# board.net
KiCad netlist of a schematic drawn in EAGLE
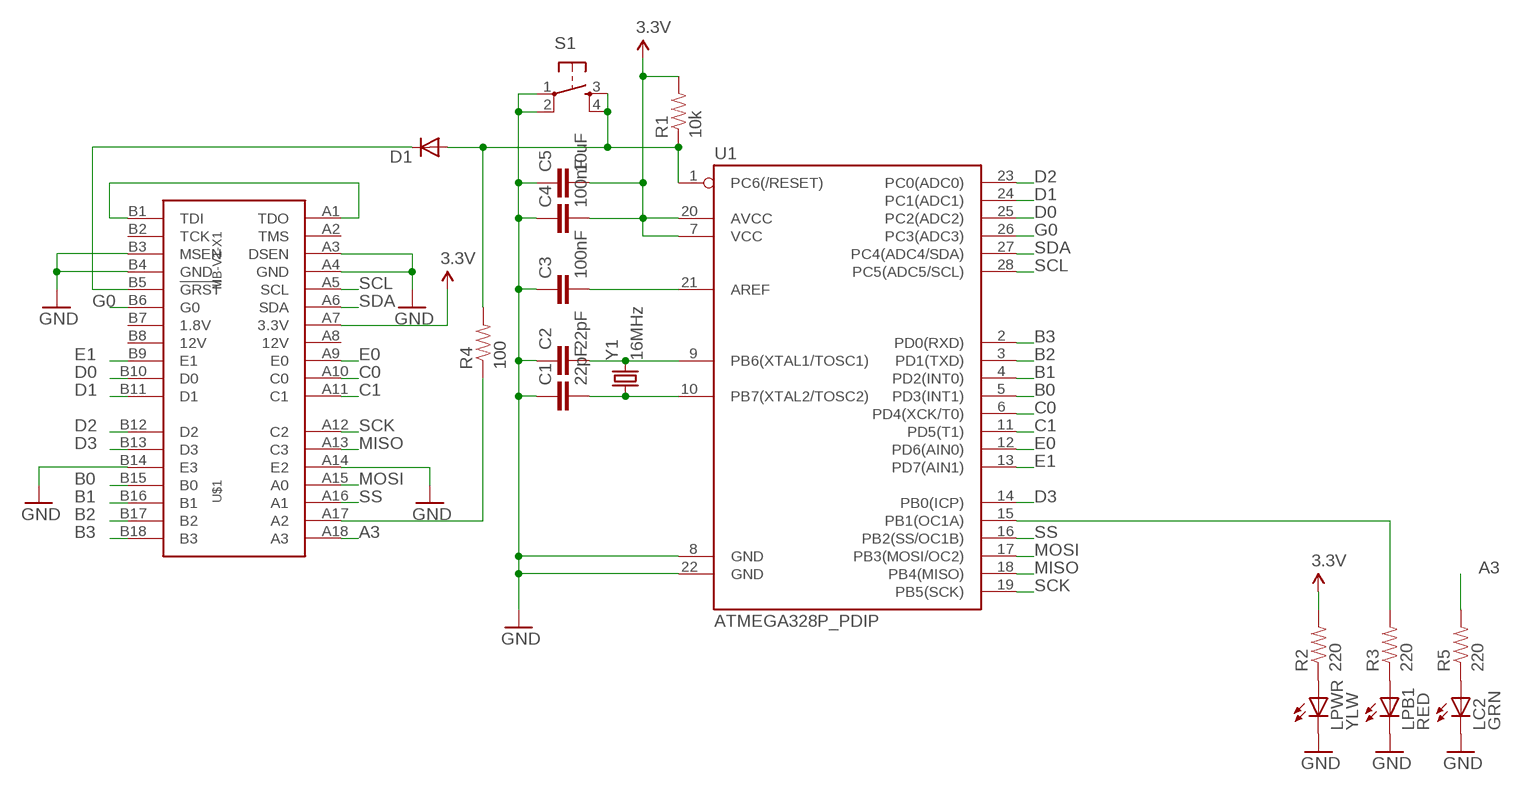
[diagram p0: schematic, sheet 1]

(export (version "E")
  (design (tool "Eeschema 10.0.6"))
  (components
    (comp (ref "C1")
      (value "22pF")
      (footprint "eagle-import:0402-CAP")
      (libsource (lib "eagle-import") (part "CAP0402-CAP"))
    )
    (comp (ref "C2")
      (value "22pF")
      (footprint "eagle-import:0402-CAP")
      (libsource (lib "eagle-import") (part "CAP0402-CAP"))
    )
    (comp (ref "C3")
      (value "100nF")
      (footprint "eagle-import:0402-CAP")
      (libsource (lib "eagle-import") (part "CAP0402-CAP"))
    )
    (comp (ref "C4")
      (value "100nF")
      (footprint "eagle-import:0402-CAP")
      (libsource (lib "eagle-import") (part "CAP0402-CAP"))
    )
    (comp (ref "C5")
      (value "10uF")
      (footprint "eagle-import:0805")
      (libsource (lib "eagle-import") (part "CAP0805"))
    )
    (comp (ref "D1")
      (value "DIODE1N4148")
      (footprint "eagle-import:DIODE-1N4148")
      (libsource (lib "eagle-import") (part "DIODE1N4148"))
    )
    (comp (ref "LC2")
      (value "GRN")
      (footprint "eagle-import:LED-0603")
      (libsource (lib "eagle-import") (part "LED-RED0603"))
    )
    (comp (ref "LPB1")
      (value "RED")
      (footprint "eagle-import:LED-0603")
      (libsource (lib "eagle-import") (part "LED-RED0603"))
    )
    (comp (ref "LPWR")
      (value "YLW")
      (footprint "eagle-import:LED-0603")
      (libsource (lib "eagle-import") (part "LED-RED0603"))
    )
    (comp (ref "R1")
      (value "10k")
      (footprint "eagle-import:0603-RES")
      (libsource (lib "eagle-import") (part "kmod-passives_RESISTOR0603"))
    )
    (comp (ref "R2")
      (value "220")
      (footprint "eagle-import:0603-RES")
      (libsource (lib "eagle-import") (part "RESISTOR0603"))
    )
    (comp (ref "R3")
      (value "220")
      (footprint "eagle-import:0603-RES")
      (libsource (lib "eagle-import") (part "RESISTOR0603"))
    )
    (comp (ref "R4")
      (value "100")
      (footprint "eagle-import:0603-RES")
      (libsource (lib "eagle-import") (part "kmod-passives_RESISTOR0603"))
    )
    (comp (ref "R5")
      (value "220")
      (footprint "eagle-import:0603-RES")
      (libsource (lib "eagle-import") (part "RESISTOR0603"))
    )
    (comp (ref "S1")
      (value "TAC_SWITCHPTH")
      (footprint "eagle-import:TACTILE-PTH")
      (libsource (lib "eagle-import") (part "TAC_SWITCHPTH"))
    )
    (comp (ref "U$1")
      (value "MB-V1-X1")
      (footprint "eagle-import:PCIE-X1-EDGE")
      (libsource (lib "eagle-import") (part "MB-V1-X1"))
    )
    (comp (ref "U1")
      (value "ATMEGA328P_PDIP")
      (footprint "eagle-import:DIL28-3")
      (libsource (lib "eagle-import") (part "ATMEGA328P_PDIP"))
    )
    (comp (ref "Y1")
      (value "16MHz")
      (footprint "eagle-import:HC49US")
      (libsource (lib "eagle-import") (part "CRYSTALHC49US"))
    )
  )
  (nets
    (net (code "1") (name "/A3") (class "Default")
      (node (ref "R5") (pin "2") (pinfunction "2_2") (pintype "passive"))
      (node (ref "U$1") (pin "A18") (pinfunction "A3_A18") (pintype "bidirectional"))
    )
    (net (code "2") (name "/B0") (class "Default")
      (node (ref "U$1") (pin "B15") (pinfunction "B0_B15") (pintype "bidirectional"))
      (node (ref "U1") (pin "5") (pinfunction "PD3(INT1)_5") (pintype "bidirectional"))
    )
    (net (code "3") (name "/B1") (class "Default")
      (node (ref "U$1") (pin "B16") (pinfunction "B1_B16") (pintype "bidirectional"))
      (node (ref "U1") (pin "4") (pinfunction "PD2(INT0)_4") (pintype "bidirectional"))
    )
    (net (code "4") (name "/B2") (class "Default")
      (node (ref "U$1") (pin "B17") (pinfunction "B2_B17") (pintype "bidirectional"))
      (node (ref "U1") (pin "3") (pinfunction "PD1(TXD)_3") (pintype "bidirectional"))
    )
    (net (code "5") (name "/B3") (class "Default")
      (node (ref "U$1") (pin "B18") (pinfunction "B3_B18") (pintype "bidirectional"))
      (node (ref "U1") (pin "2") (pinfunction "PD0(RXD)_2") (pintype "bidirectional"))
    )
    (net (code "6") (name "/C0") (class "Default")
      (node (ref "U$1") (pin "A10") (pinfunction "C0_A10") (pintype "bidirectional"))
      (node (ref "U1") (pin "6") (pinfunction "PD4(XCK/T0)_6") (pintype "bidirectional"))
    )
    (net (code "7") (name "/C1") (class "Default")
      (node (ref "U$1") (pin "A11") (pinfunction "C1_A11") (pintype "bidirectional"))
      (node (ref "U1") (pin "11") (pinfunction "PD5(T1)_11") (pintype "bidirectional"))
    )
    (net (code "8") (name "/D0") (class "Default")
      (node (ref "U$1") (pin "B10") (pinfunction "D0_B10") (pintype "bidirectional"))
      (node (ref "U1") (pin "25") (pinfunction "PC2(ADC2)_25") (pintype "bidirectional"))
    )
    (net (code "9") (name "/D1") (class "Default")
      (node (ref "U$1") (pin "B11") (pinfunction "D1_B11") (pintype "bidirectional"))
      (node (ref "U1") (pin "24") (pinfunction "PC1(ADC1)_24") (pintype "bidirectional"))
    )
    (net (code "10") (name "/D2") (class "Default")
      (node (ref "U$1") (pin "B12") (pinfunction "D2_B12") (pintype "bidirectional"))
      (node (ref "U1") (pin "23") (pinfunction "PC0(ADC0)_23") (pintype "bidirectional"))
    )
    (net (code "11") (name "/D3") (class "Default")
      (node (ref "U$1") (pin "B13") (pinfunction "D3_B13") (pintype "bidirectional"))
      (node (ref "U1") (pin "14") (pinfunction "PB0(ICP)_14") (pintype "bidirectional"))
    )
    (net (code "12") (name "/E0") (class "Default")
      (node (ref "U$1") (pin "A9") (pinfunction "E0_A9") (pintype "bidirectional"))
      (node (ref "U1") (pin "12") (pinfunction "PD6(AIN0)_12") (pintype "bidirectional"))
    )
    (net (code "13") (name "/E1") (class "Default")
      (node (ref "U$1") (pin "B9") (pinfunction "E1_B9") (pintype "bidirectional"))
      (node (ref "U1") (pin "13") (pinfunction "PD7(AIN1)_13") (pintype "bidirectional"))
    )
    (net (code "14") (name "/G0") (class "Default")
      (node (ref "U$1") (pin "B6") (pinfunction "G0_B6") (pintype "bidirectional"))
      (node (ref "U1") (pin "26") (pinfunction "PC3(ADC3)_26") (pintype "bidirectional"))
    )
    (net (code "15") (name "/MISO") (class "Default")
      (node (ref "U$1") (pin "A13") (pinfunction "C3_A13") (pintype "bidirectional"))
      (node (ref "U1") (pin "18") (pinfunction "PB4(MISO)_18") (pintype "bidirectional"))
    )
    (net (code "16") (name "/MOSI") (class "Default")
      (node (ref "U$1") (pin "A15") (pinfunction "A0_A15") (pintype "bidirectional"))
      (node (ref "U1") (pin "17") (pinfunction "PB3(MOSI/OC2)_17") (pintype "bidirectional"))
    )
    (net (code "17") (name "/SCK") (class "Default")
      (node (ref "U$1") (pin "A12") (pinfunction "C2_A12") (pintype "bidirectional"))
      (node (ref "U1") (pin "19") (pinfunction "PB5(SCK)_19") (pintype "bidirectional"))
    )
    (net (code "18") (name "/SCL") (class "Default")
      (node (ref "U$1") (pin "A5") (pinfunction "SCL_A5") (pintype "bidirectional"))
      (node (ref "U1") (pin "28") (pinfunction "PC5(ADC5/SCL)_28") (pintype "bidirectional"))
    )
    (net (code "19") (name "/SDA") (class "Default")
      (node (ref "U$1") (pin "A6") (pinfunction "SDA_A6") (pintype "bidirectional"))
      (node (ref "U1") (pin "27") (pinfunction "PC4(ADC4/SDA)_27") (pintype "bidirectional"))
    )
    (net (code "20") (name "/SS") (class "Default")
      (node (ref "U$1") (pin "A16") (pinfunction "A1_A16") (pintype "bidirectional"))
      (node (ref "U1") (pin "16") (pinfunction "PB2(SS/OC1B)_16") (pintype "bidirectional"))
    )
    (net (code "21") (name "3.3V") (class "Default")
      (node (ref "C4") (pin "2") (pinfunction "2_2") (pintype "passive"))
      (node (ref "C5") (pin "2") (pinfunction "2_2") (pintype "passive"))
      (node (ref "R1") (pin "2") (pinfunction "2_2") (pintype "passive"))
      (node (ref "R2") (pin "2") (pinfunction "2_2") (pintype "passive"))
      (node (ref "U$1") (pin "A7") (pinfunction "3.3V_A7") (pintype "bidirectional"))
      (node (ref "U1") (pin "20") (pinfunction "AVCC_20") (pintype "bidirectional"))
      (node (ref "U1") (pin "7") (pinfunction "VCC_7") (pintype "bidirectional"))
    )
    (net (code "22") (name "GND") (class "Default")
      (node (ref "C1") (pin "1") (pinfunction "1_1") (pintype "passive"))
      (node (ref "C2") (pin "1") (pinfunction "1_1") (pintype "passive"))
      (node (ref "C3") (pin "1") (pinfunction "1_1") (pintype "passive"))
      (node (ref "C4") (pin "1") (pinfunction "1_1") (pintype "passive"))
      (node (ref "C5") (pin "1") (pinfunction "1_1") (pintype "passive"))
      (node (ref "LC2") (pin "C") (pinfunction "C_C") (pintype "passive"))
      (node (ref "LPB1") (pin "C") (pinfunction "C_C") (pintype "passive"))
      (node (ref "LPWR") (pin "C") (pinfunction "C_C") (pintype "passive"))
      (node (ref "S1") (pin "1") (pinfunction "1_1") (pintype "passive"))
      (node (ref "S1") (pin "2") (pinfunction "2_2") (pintype "passive"))
      (node (ref "U$1") (pin "A14") (pinfunction "E2_A14") (pintype "bidirectional"))
      (node (ref "U$1") (pin "A3") (pinfunction "DSEN_A3") (pintype "bidirectional"))
      (node (ref "U$1") (pin "A4") (pinfunction "GND_A4") (pintype "bidirectional"))
      (node (ref "U$1") (pin "B14") (pinfunction "E3_B14") (pintype "bidirectional"))
      (node (ref "U$1") (pin "B3") (pinfunction "MSEN_B3") (pintype "bidirectional"))
      (node (ref "U$1") (pin "B4") (pinfunction "GND_B4") (pintype "bidirectional"))
      (node (ref "U1") (pin "22") (pinfunction "GND_22") (pintype "bidirectional"))
      (node (ref "U1") (pin "8") (pinfunction "GND_8") (pintype "bidirectional"))
    )
    (net (code "23") (name "Net-(LC2-PadA)") (class "Default")
      (node (ref "LC2") (pin "A") (pinfunction "A_A") (pintype "passive"))
      (node (ref "R5") (pin "1") (pinfunction "1_1") (pintype "passive"))
    )
    (net (code "24") (name "Net-(LPB1-PadA)") (class "Default")
      (node (ref "LPB1") (pin "A") (pinfunction "A_A") (pintype "passive"))
      (node (ref "R3") (pin "1") (pinfunction "1_1") (pintype "passive"))
    )
    (net (code "25") (name "Net-(LPWR-PadA)") (class "Default")
      (node (ref "LPWR") (pin "A") (pinfunction "A_A") (pintype "passive"))
      (node (ref "R2") (pin "1") (pinfunction "1_1") (pintype "passive"))
    )
    (net (code "26") (name "Net-(U$1-A2)") (class "Default")
      (node (ref "R4") (pin "1") (pinfunction "1_1") (pintype "passive"))
      (node (ref "U$1") (pin "A17") (pinfunction "A2_A17") (pintype "bidirectional"))
    )
    (net (code "27") (name "Net-(U$1-TDI)") (class "Default")
      (node (ref "U$1") (pin "A1") (pinfunction "TDO_A1") (pintype "bidirectional"))
      (node (ref "U$1") (pin "B1") (pinfunction "TDI_B1") (pintype "bidirectional"))
    )
    (net (code "28") (name "Net-(U$1-~{GRST})") (class "Default")
      (node (ref "D1") (pin "C") (pinfunction "C_C") (pintype "passive"))
      (node (ref "U$1") (pin "B5") (pinfunction "~{GRST}_B5") (pintype "bidirectional"))
    )
    (net (code "29") (name "Net-(U1-AREF)") (class "Default")
      (node (ref "C3") (pin "2") (pinfunction "2_2") (pintype "passive"))
      (node (ref "U1") (pin "21") (pinfunction "AREF_21") (pintype "bidirectional"))
    )
    (net (code "30") (name "Net-(U1-PB1(OC1A))") (class "Default")
      (node (ref "R3") (pin "2") (pinfunction "2_2") (pintype "passive"))
      (node (ref "U1") (pin "15") (pinfunction "PB1(OC1A)_15") (pintype "bidirectional"))
    )
    (net (code "31") (name "Net-(U1-PB6(XTAL1{slash}TOSC1))") (class "Default")
      (node (ref "C2") (pin "2") (pinfunction "2_2") (pintype "passive"))
      (node (ref "U1") (pin "9") (pinfunction "PB6(XTAL1/TOSC1)_9") (pintype "bidirectional"))
      (node (ref "Y1") (pin "2") (pinfunction "2_2") (pintype "passive"))
    )
    (net (code "32") (name "Net-(U1-PB7(XTAL2{slash}TOSC2))") (class "Default")
      (node (ref "C1") (pin "2") (pinfunction "2_2") (pintype "passive"))
      (node (ref "U1") (pin "10") (pinfunction "PB7(XTAL2/TOSC2)_10") (pintype "bidirectional"))
      (node (ref "Y1") (pin "1") (pinfunction "1_1") (pintype "passive"))
    )
    (net (code "33") (name "Net-(U1-PC6({slash}RESET))") (class "Default")
      (node (ref "D1") (pin "A") (pinfunction "A_A") (pintype "passive"))
      (node (ref "R1") (pin "1") (pinfunction "1_1") (pintype "passive"))
      (node (ref "R4") (pin "2") (pinfunction "2_2") (pintype "passive"))
      (node (ref "S1") (pin "3") (pinfunction "3_3") (pintype "passive"))
      (node (ref "S1") (pin "4") (pinfunction "4_4") (pintype "passive"))
      (node (ref "U1") (pin "1") (pinfunction "PC6(/RESET)_1") (pintype "bidirectional"))
    )
    (net (code "34") (name "unconnected-(U$1-1.8V-PadB7)") (class "Default")
      (node (ref "U$1") (pin "B7") (pinfunction "1.8V_B7") (pintype "bidirectional"))
    )
    (net (code "35") (name "unconnected-(U$1-12V-PadA8)") (class "Default")
      (node (ref "U$1") (pin "A8") (pinfunction "12V_A8") (pintype "bidirectional"))
    )
    (net (code "36") (name "unconnected-(U$1-12V-PadB8)") (class "Default")
      (node (ref "U$1") (pin "B8") (pinfunction "12V_B8") (pintype "bidirectional"))
    )
    (net (code "37") (name "unconnected-(U$1-TCK-PadB2)") (class "Default")
      (node (ref "U$1") (pin "B2") (pinfunction "TCK_B2") (pintype "bidirectional"))
    )
    (net (code "38") (name "unconnected-(U$1-TMS-PadA2)") (class "Default")
      (node (ref "U$1") (pin "A2") (pinfunction "TMS_A2") (pintype "bidirectional"))
    )
  )
)
